# sr_indicator_v0_revB.net
KiCad netlist of a schematic drawn in EAGLE
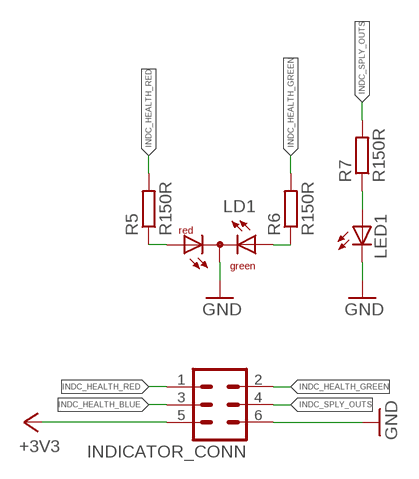
[diagram p0: schematic, sheet 1]

(export (version "E")
  (design (tool "Eeschema 10.0.6"))
  (components
    (comp (ref "INDICATOR_CONN")
      (value "MA03-2")
      (footprint "eagle-import:MA03-2")
      (libsource (lib "eagle-import") (part "MA03-2"))
    )
    (comp (ref "LD1")
      (value "DUOLED-RG-C")
      (footprint "eagle-import:DUOLED-C-5MM")
      (libsource (lib "eagle-import") (part "DUOLED-RG-C"))
    )
    (comp (ref "LED1")
      (value "LED5MM")
      (footprint "eagle-import:LED5MM")
      (libsource (lib "eagle-import") (part "LED5MM"))
    )
    (comp (ref "R5")
      (value "R150R")
      (footprint "eagle-import:M0805")
      (libsource (lib "eagle-import") (part "R-EU_M0805"))
    )
    (comp (ref "R6")
      (value "R150R")
      (footprint "eagle-import:M0805")
      (libsource (lib "eagle-import") (part "R-EU_M0805"))
    )
    (comp (ref "R7")
      (value "R150R")
      (footprint "eagle-import:M0805")
      (libsource (lib "eagle-import") (part "R-EU_M0805"))
    )
  )
  (nets
    (net (code "1") (name "+3V3") (class "Default")
      (node (ref "INDICATOR_CONN") (pin "5") (pinfunction "5_5") (pintype "passive"))
    )
    (net (code "2") (name "GND") (class "Default")
      (node (ref "INDICATOR_CONN") (pin "6") (pinfunction "6_6") (pintype "passive"))
      (node (ref "LD1") (pin "C") (pinfunction "C_C") (pintype "passive"))
      (node (ref "LED1") (pin "K") (pinfunction "C_K") (pintype "passive"))
    )
    (net (code "3") (name "INDC_HEALTH_BLUE") (class "Default")
      (node (ref "INDICATOR_CONN") (pin "3") (pinfunction "3_3") (pintype "passive"))
    )
    (net (code "4") (name "INDC_HEALTH_GREEN") (class "Default")
      (node (ref "INDICATOR_CONN") (pin "2") (pinfunction "2_2") (pintype "passive"))
      (node (ref "R6") (pin "2") (pinfunction "2_2") (pintype "passive"))
    )
    (net (code "5") (name "INDC_HEALTH_RED") (class "Default")
      (node (ref "INDICATOR_CONN") (pin "1") (pinfunction "1_1") (pintype "passive"))
      (node (ref "R5") (pin "2") (pinfunction "2_2") (pintype "passive"))
    )
    (net (code "6") (name "INDC_SPLY_OUTS") (class "Default")
      (node (ref "INDICATOR_CONN") (pin "4") (pinfunction "4_4") (pintype "passive"))
      (node (ref "R7") (pin "2") (pinfunction "2_2") (pintype "passive"))
    )
    (net (code "7") (name "Net-(LD1-AG)") (class "Default")
      (node (ref "LD1") (pin "AX") (pinfunction "AG_AX") (pintype "passive"))
      (node (ref "R6") (pin "1") (pinfunction "1_1") (pintype "passive"))
    )
    (net (code "8") (name "Net-(LD1-PadAR)") (class "Default")
      (node (ref "LD1") (pin "AR") (pinfunction "AR_AR") (pintype "passive"))
      (node (ref "R5") (pin "1") (pinfunction "1_1") (pintype "passive"))
    )
    (net (code "9") (name "Net-(LED1-PadA)") (class "Default")
      (node (ref "LED1") (pin "A") (pinfunction "A_A") (pintype "passive"))
      (node (ref "R7") (pin "1") (pinfunction "1_1") (pintype "passive"))
    )
  )
)
